# DIMNode012014.net
KiCad netlist of a schematic drawn in Altium Designer
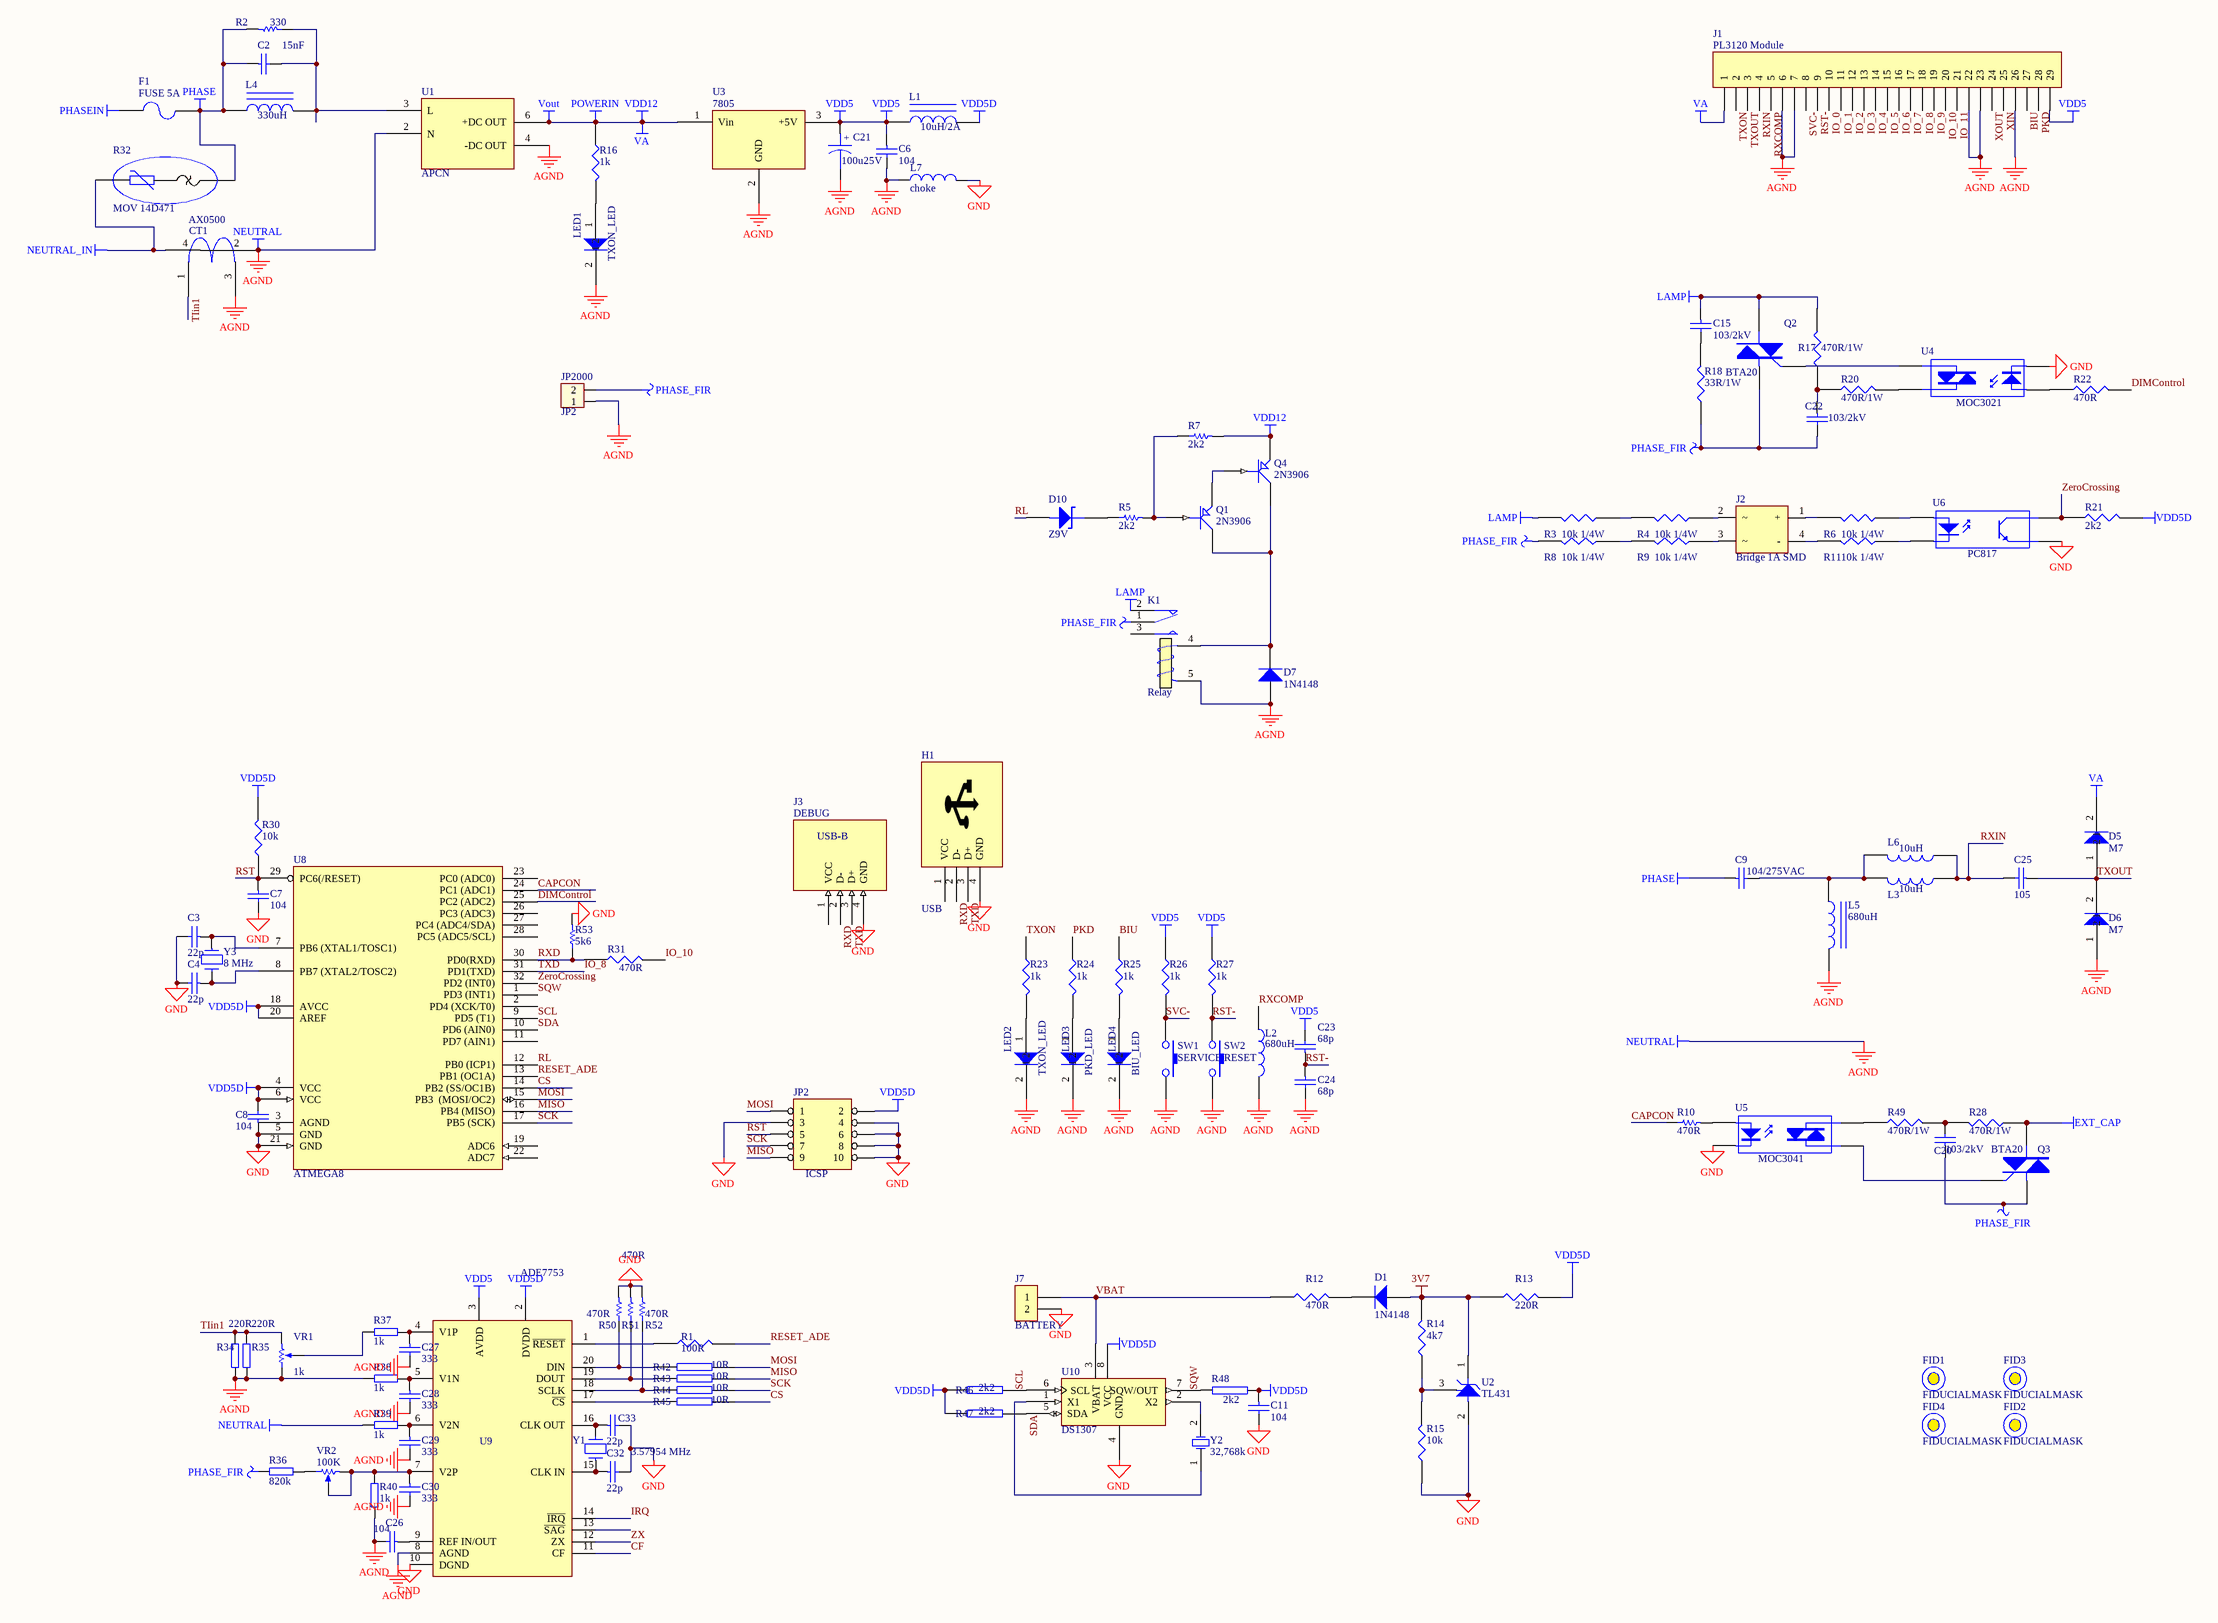
[diagram p0: DIMNode012014.SchDoc]

(export (version "E")
  (design (tool "Eeschema 10.0.6"))
  (components
    (comp (ref "C2")
      (value "15nF")
      (footprint "CAPNTO5.08-7.37x3.94")
      (description "Capacitor")
      (libsource (lib "") (part "CAP_1"))
    )
    (comp (ref "C3") (value "22p") (footprint "2012[0805]") (libsource (lib "*") (part "CAP")))
    (comp (ref "C4") (value "22p") (footprint "2012[0805]") (libsource (lib "*") (part "CAP")))
    (comp (ref "C6")
      (value "104")
      (footprint "2012[0805]")
      (description "Capacitor")
      (libsource (lib "") (part "CAP_1"))
    )
    (comp (ref "C7")
      (value "104")
      (footprint "2012[0805]")
      (description "Capacitor")
      (libsource (lib "") (part "CAP_1"))
    )
    (comp (ref "C8")
      (value "104")
      (footprint "2012[0805]")
      (description "Capacitor")
      (libsource (lib "") (part "CAP_1"))
    )
    (comp (ref "C9")
      (value "104/275VAC")
      (footprint "100n400v")
      (description "Capacitor")
      (libsource (lib "") (part "CAP_1"))
    )
    (comp (ref "C11")
      (value "104")
      (footprint "2012[0805]")
      (description "Capacitor")
      (libsource (lib "") (part "CAP_1"))
    )
    (comp (ref "C15")
      (value "103/2kV")
      (footprint "104TO")
      (description "Capacitor")
      (libsource (lib "") (part "CAP_1"))
    )
    (comp (ref "C20")
      (value "103/2kV")
      (footprint "104TO")
      (description "Capacitor")
      (libsource (lib "") (part "CAP_1"))
    )
    (comp (ref "C21")
      (value "100u25V")
      (footprint "TC7360-2924")
      (description "Capacitor")
      (libsource (lib "*") (part "CAPACITOR POL"))
    )
    (comp (ref "C22")
      (value "103/2kV")
      (footprint "104TO")
      (description "Capacitor")
      (libsource (lib "") (part "CAP_1"))
    )
    (comp (ref "C23")
      (value "68p")
      (footprint "2012[0805]")
      (description "Capacitor")
      (libsource (lib "") (part "CAP_1"))
    )
    (comp (ref "C24")
      (value "68p")
      (footprint "2012[0805]")
      (description "Capacitor")
      (libsource (lib "") (part "CAP_1"))
    )
    (comp (ref "C25")
      (value "105")
      (footprint "CSIP3")
      (description "Capacitor")
      (libsource (lib "") (part "CAP_1"))
    )
    (comp (ref "C26") (value "104") (footprint "2012[0805]") (libsource (lib "*") (part "CAP")))
    (comp (ref "C27") (value "333") (footprint "2012[0805]") (libsource (lib "*") (part "CAP")))
    (comp (ref "C28") (value "333") (footprint "2012[0805]") (libsource (lib "*") (part "CAP")))
    (comp (ref "C29") (value "333") (footprint "2012[0805]") (libsource (lib "*") (part "CAP")))
    (comp (ref "C30") (value "333") (footprint "2012[0805]") (libsource (lib "*") (part "CAP")))
    (comp (ref "C32") (value "22p") (footprint "2012[0805]") (libsource (lib "*") (part "CAP")))
    (comp (ref "C33") (value "22p") (footprint "2012[0805]") (libsource (lib "*") (part "CAP")))
    (comp (ref "CT1") (value "AX0500") (footprint "CT-NHO") (libsource (lib "Schlib1") (part "AX-0500")))
    (comp (ref "D1")
      (value "1N4148")
      (footprint "SOD-80/MLL34")
      (description "1 Amp General Purpose Rectifier")
      (fields (field (name "PUBLISHER") "Altium Limited"))
      (libsource (lib "*") (part "Diode 1N4007"))
    )
    (comp (ref "D5") (value "M7") (footprint "MELF-D5022-2009") (libsource (lib "*") (part "DIODE")))
    (comp (ref "D6") (value "M7") (footprint "MELF-D5022-2009") (libsource (lib "*") (part "DIODE")))
    (comp (ref "D7")
      (value "1N4148")
      (footprint "SOD-80/MLL34")
      (description "1 Amp General Purpose Rectifier")
      (fields (field (name "PUBLISHER") "Altium Limited"))
      (libsource (lib "*") (part "Diode 1N4007"))
    )
    (comp (ref "D10")
      (value "Z9V")
      (footprint "SOD-80/MLL34")
      (description "Zener Diode")
      (libsource (lib "*") (part "ZENER2"))
    )
    (comp (ref "F1")
      (value "FUSE 5A")
      (footprint "FUSE2")
      (description "Fuse")
      (libsource (lib "*") (part "FUSE2"))
    )
    (comp (ref "FID1")
      (value "FIDUCIALMASK")
      (footprint "FIDUCIALMASK")
      (libsource (lib "*") (part "FIDUCIALMASK"))
    )
    (comp (ref "FID2")
      (value "FIDUCIALMASK")
      (footprint "FIDUCIALMASK")
      (libsource (lib "*") (part "FIDUCIALMASK"))
    )
    (comp (ref "FID3")
      (value "FIDUCIALMASK")
      (footprint "FIDUCIALMASK")
      (libsource (lib "*") (part "FIDUCIALMASK"))
    )
    (comp (ref "FID4")
      (value "FIDUCIALMASK")
      (footprint "FIDUCIALMASK")
      (libsource (lib "*") (part "FIDUCIALMASK"))
    )
    (comp (ref "H1") (value "USB") (footprint "USB-B-STRANGE") (libsource (lib "Schematic") (part "USB")))
    (comp (ref "J1")
      (value "PL3120 Module")
      (footprint "ECHELONMODULE")
      (description "Connector")
      (libsource (lib "*") (part "CON29"))
    )
    (comp (ref "J2")
      (value "Bridge 1A SMD")
      (footprint "CAUSMD")
      (description "Diode Bridge")
      (libsource (lib "Schematic") (part "Diode Bridge Flate"))
    )
    (comp (ref "J3") (value "DEBUG") (footprint "SJ-3515") (libsource (lib "*") (part "USB_B")))
    (comp (ref "J7")
      (value "BATTERY")
      (footprint "pincucao")
      (description "Connector")
      (libsource (lib "*") (part "CON2"))
    )
    (comp (ref "JP2") (value "ICSP") (footprint "IDC10") (libsource (lib "*") (part "HEADER 5X2")))
    (comp (ref "JP2000")
      (value "JP2")
      (footprint "HED2")
      (description "Connector 2")
      (libsource (lib "syhaunguyen") (part "Con2"))
    )
    (comp (ref "K1")
      (value "Relay")
      (footprint "Relayvuong")
      (description "SPDT Relay")
      (fields (field (name "PUBLISHER") "Altium Limited"))
      (libsource (lib "*") (part "Relay"))
    )
    (comp (ref "L1") (value "10uH/2A") (libsource (lib "*") (part "INDUCTOR IRON")))
    (comp (ref "L2") (value "680uH") (footprint "AXIAL0.4") (libsource (lib "*") (part "INDUCTOR")))
    (comp (ref "L3") (value "10uH") (footprint "AXIAL0.4") (libsource (lib "*") (part "INDUCTOR")))
    (comp (ref "L4") (value "330uH") (footprint "CAMTRONDUNG") (libsource (lib "*") (part "INDUCTOR IRON")))
    (comp (ref "L5") (value "680uH") (footprint "axial0.4") (libsource (lib "*") (part "INDUCTOR IRON")))
    (comp (ref "L6") (value "10uH") (footprint "AXIAL0.4") (libsource (lib "*") (part "INDUCTOR")))
    (comp (ref "L7")
      (value "choke")
      (footprint "axial0.3")
      (fields (field (name "PUBLISHER") "Altium Limited"))
      (libsource (lib "Miscellaneous Devices") (part "Inductor"))
    )
    (comp (ref "LED1") (value "TXON_LED") (footprint "LED0805") (libsource (lib "*") (part "DIODE")))
    (comp (ref "LED2") (value "TXON_LED") (footprint "LED0805") (libsource (lib "*") (part "DIODE")))
    (comp (ref "LED3") (value "PKD_LED") (footprint "LED0805") (libsource (lib "*") (part "DIODE")))
    (comp (ref "LED4") (value "BIU_LED") (footprint "LED0805") (libsource (lib "*") (part "DIODE")))
    (comp (ref "Q1")
      (value "2N3906")
      (footprint "SOT-23")
      (description "PNP Transistor")
      (libsource (lib "*") (part "PNP1"))
    )
    (comp (ref "Q2") (value "BTA20") (footprint "TO254") (libsource (lib "*") (part "TRIAC")))
    (comp (ref "Q3") (value "BTA20") (footprint "TO254") (libsource (lib "*") (part "TRIAC")))
    (comp (ref "Q4")
      (value "2N3906")
      (footprint "SOT-23")
      (description "PNP Transistor")
      (libsource (lib "*") (part "PNP1"))
    )
    (comp (ref "R1") (value "100R") (footprint "2012[0805]") (libsource (lib "*") (part "RES1")))
    (comp (ref "R2")
      (value "330")
      (footprint "3216[1206]")
      (description "Semiconductor Resistor")
      (fields (field (name "PUBLISHER") "Altium Limited"))
      (libsource (lib "*") (part "Res Semi"))
    )
    (comp (ref "R3") (value "10k 1/4W") (footprint "3216[1206]") (libsource (lib "*") (part "RES1")))
    (comp (ref "R4") (value "10k 1/4W") (footprint "3216[1206]") (libsource (lib "*") (part "RES1")))
    (comp (ref "R5")
      (value "2k2")
      (footprint "2012[0805]")
      (description "Semiconductor Resistor")
      (fields (field (name "PUBLISHER") "Altium Limited"))
      (libsource (lib "*") (part "Res Semi"))
    )
    (comp (ref "R6") (value "10k 1/4W") (footprint "3216[1206]") (libsource (lib "*") (part "RES1")))
    (comp (ref "R7")
      (value "2k2")
      (footprint "2012[0805]")
      (description "Semiconductor Resistor")
      (fields (field (name "PUBLISHER") "Altium Limited"))
      (libsource (lib "*") (part "Res Semi"))
    )
    (comp (ref "R8") (value "10k 1/4W") (footprint "3216[1206]") (libsource (lib "*") (part "RES1")))
    (comp (ref "R9") (value "10k 1/4W") (footprint "3216[1206]") (libsource (lib "*") (part "RES1")))
    (comp (ref "R10")
      (value "470R")
      (footprint "2012[0805]")
      (description "Semiconductor Resistor")
      (fields (field (name "PUBLISHER") "Altium Limited"))
      (libsource (lib "*") (part "Res Semi"))
    )
    (comp (ref "R11") (value "10k 1/4W") (footprint "3216[1206]") (libsource (lib "*") (part "RES1")))
    (comp (ref "R12") (value "470R") (footprint "2012[0805]") (libsource (lib "*") (part "RES1")))
    (comp (ref "R13") (value "220R") (footprint "2012[0805]") (libsource (lib "*") (part "RES1")))
    (comp (ref "R14") (value "4k7") (footprint "2012[0805]") (libsource (lib "*") (part "RES1")))
    (comp (ref "R15") (value "10k") (footprint "2012[0805]") (libsource (lib "*") (part "RES1")))
    (comp (ref "R16") (value "1k") (footprint "2012[0805]") (libsource (lib "*") (part "RES1")))
    (comp (ref "R17") (value "470R/1W") (footprint "AXIAL0.5") (libsource (lib "*") (part "RES1")))
    (comp (ref "R18") (value "33R/1W") (footprint "R1W_dung") (libsource (lib "*") (part "RES1")))
    (comp (ref "R20") (value "470R/1W") (footprint "R1W_DUNG") (libsource (lib "*") (part "RES1")))
    (comp (ref "R21") (value "2k2") (footprint "2012[0805]") (libsource (lib "*") (part "RES1")))
    (comp (ref "R22") (value "470R") (footprint "2012[0805]") (libsource (lib "*") (part "RES1")))
    (comp (ref "R23") (value "1k") (footprint "2012[0805]") (libsource (lib "*") (part "RES1")))
    (comp (ref "R24") (value "1k") (footprint "2012[0805]") (libsource (lib "*") (part "RES1")))
    (comp (ref "R25") (value "1k") (footprint "2012[0805]") (libsource (lib "*") (part "RES1")))
    (comp (ref "R26") (value "1k") (footprint "2012[0805]") (libsource (lib "*") (part "RES1")))
    (comp (ref "R27") (value "1k") (footprint "2012[0805]") (libsource (lib "*") (part "RES1")))
    (comp (ref "R28") (value "470R/1W") (footprint "R1W_dung") (libsource (lib "*") (part "RES1")))
    (comp (ref "R30") (value "10k") (footprint "2012[0805]") (libsource (lib "*") (part "RES1")))
    (comp (ref "R31") (value "470R") (footprint "2012[0805]") (libsource (lib "*") (part "RES1")))
    (comp (ref "R32") (value "MOV 14D471") (footprint "MOV471") (libsource (lib "*") (part "MOV")))
    (comp (ref "R34") (value "220R") (footprint "2012[0805]") (libsource (lib "") (part "RES2_1")))
    (comp (ref "R35") (value "220R") (footprint "2012[0805]") (libsource (lib "") (part "RES2_1")))
    (comp (ref "R36") (value "820k") (footprint "1206") (libsource (lib "") (part "RES2_1")))
    (comp (ref "R37") (value "1k") (footprint "2012[0805]") (libsource (lib "") (part "RES2_1")))
    (comp (ref "R38") (value "1k") (footprint "2012[0805]") (libsource (lib "") (part "RES2_1")))
    (comp (ref "R39") (value "1k") (footprint "2012[0805]") (libsource (lib "") (part "RES2_1")))
    (comp (ref "R40") (value "1k") (footprint "2012[0805]") (libsource (lib "") (part "RES2_1")))
    (comp (ref "R42") (value "10R") (footprint "2012[0805]") (libsource (lib "*") (part "RES2")))
    (comp (ref "R43") (value "10R") (footprint "2012[0805]") (libsource (lib "*") (part "RES2")))
    (comp (ref "R44") (value "10R") (footprint "2012[0805]") (libsource (lib "*") (part "RES2")))
    (comp (ref "R45") (value "10R") (footprint "2012[0805]") (libsource (lib "*") (part "RES2")))
    (comp (ref "R46") (value "2k2") (footprint "2012[0805]") (libsource (lib "*") (part "RES2")))
    (comp (ref "R47") (value "2k2") (footprint "2012[0805]") (libsource (lib "*") (part "RES2")))
    (comp (ref "R48") (value "2k2") (footprint "2012[0805]") (libsource (lib "") (part "RES2_2")))
    (comp (ref "R49") (value "470R/1W") (footprint "R1W_DUNG") (libsource (lib "*") (part "RES1")))
    (comp (ref "R50")
      (value "470R")
      (footprint "2012[0805]")
      (description "Semiconductor Resistor")
      (fields (field (name "PUBLISHER") "*"))
      (libsource (lib "*") (part "Res Semi"))
    )
    (comp (ref "R51")
      (value "470R")
      (footprint "2012[0805]")
      (description "Semiconductor Resistor")
      (fields (field (name "PUBLISHER") "*"))
      (libsource (lib "*") (part "Res Semi"))
    )
    (comp (ref "R52")
      (value "470R")
      (footprint "2012[0805]")
      (description "Semiconductor Resistor")
      (fields (field (name "PUBLISHER") "*"))
      (libsource (lib "*") (part "Res Semi"))
    )
    (comp (ref "R53")
      (value "5k6")
      (footprint "2012[0805]")
      (description "Semiconductor Resistor")
      (fields (field (name "PUBLISHER") "*"))
      (libsource (lib "*") (part "Res Semi"))
    )
    (comp (ref "SW1") (value "SERVICE") (footprint "CTCHIPNGANG") (libsource (lib "*") (part "SW-PB")))
    (comp (ref "SW2") (value "RESET") (footprint "CTCHIPNGANG") (libsource (lib "*") (part "SW-PB")))
    (comp (ref "U1") (value "APCN") (footprint "APCN") (libsource (lib "Node v2013") (part "Component_1")))
    (comp (ref "U2")
      (value "TL431")
      (footprint "TL431")
      (description "Adjustable Precision Shunt Regulator")
      (libsource (lib "*") (part "TL431"))
    )
    (comp (ref "U3") (value "7805") (footprint "J7805") (libsource (lib "*") (part "MC7805T")))
    (comp (ref "U4") (value "MOC3021") (footprint "DIP6") (libsource (lib "*") (part "OPTOTRIAC")))
    (comp (ref "U5") (value "MOC3041") (footprint "DIP6") (libsource (lib "*") (part "OPTOTRIAC")))
    (comp (ref "U6")
      (value "PC817")
      (footprint "TLP521")
      (description "Optoisolator")
      (libsource (lib "*") (part "OPTOISO1"))
    )
    (comp (ref "U8")
      (value "ATMEGA8")
      (footprint "ATMEGA8")
      (description "TQFP package")
      (libsource (lib "*") (part "ATMEGA8-A"))
    )
    (comp (ref "U9") (value "ADE7753") (footprint "ADE775X") (libsource (lib "*") (part "ADE775X")))
    (comp (ref "U10")
      (value "DS1307")
      (footprint "SO-8")
      (description "64x8 SERIAL REAL TIME CLOCK")
      (libsource (lib "*") (part "DS1307(8)"))
    )
    (comp (ref "VR1")
      (value "1k")
      (footprint "BTXANH")
      (description "Potentiometer")
      (fields (field (name "PUBLISHER") "*"))
      (libsource (lib "*") (part "RPot"))
    )
    (comp (ref "VR2")
      (value "100K")
      (footprint "BTXANH")
      (description "Potentiometer")
      (fields (field (name "PUBLISHER") "*"))
      (libsource (lib "*") (part "RPot"))
    )
    (comp (ref "Y1")
      (value "3.57954 MHz")
      (footprint "XTAL")
      (description "Crystal")
      (libsource (lib "*") (part "CRYSTAL"))
    )
    (comp (ref "Y2")
      (value "32,768k")
      (footprint "R38")
      (description "Crystal Oscillator")
      (fields (field (name "PUBLISHER") "Altium Limited"))
      (libsource (lib "Miscellaneous Devices") (part "XTAL"))
    )
    (comp (ref "Y3")
      (value "8 MHz")
      (footprint "XTAL")
      (description "Crystal")
      (libsource (lib "*") (part "CRYSTAL"))
    )
  )
  (nets
    (net (code "1") (name "/BIU") (class "Default")
      (node (ref "J1") (pin "27") (pinfunction "27_27") (pintype "passive"))
      (node (ref "R25") (pin "1") (pinfunction "1_1") (pintype "passive"))
    )
    (net (code "2") (name "/CAPCON") (class "Default")
      (node (ref "R10") (pin "1") (pinfunction "1_1") (pintype "passive"))
      (node (ref "U8") (pin "24") (pinfunction "PC1_(ADC1)_24") (pintype "passive"))
    )
    (net (code "3") (name "/CF") (class "Default")
      (node (ref "U9") (pin "11") (pinfunction "CF_11") (pintype "passive"))
    )
    (net (code "4") (name "/CS") (class "Default")
      (node (ref "R45") (pin "1") (pinfunction "1_1") (pintype "passive"))
      (node (ref "U8") (pin "14") (pinfunction "PB2_(SS/OC1B)_14") (pintype "passive"))
    )
    (net (code "5") (name "/DIMControl") (class "Default")
      (node (ref "R22") (pin "2") (pinfunction "2_2") (pintype "passive"))
      (node (ref "U8") (pin "25") (pinfunction "PC2_(ADC2)_25") (pintype "passive"))
    )
    (net (code "6") (name "/IO_0") (class "Default")
      (node (ref "J1") (pin "10") (pinfunction "10_10") (pintype "passive"))
    )
    (net (code "7") (name "/IO_1") (class "Default")
      (node (ref "J1") (pin "11") (pinfunction "11_11") (pintype "passive"))
    )
    (net (code "8") (name "/IO_2") (class "Default")
      (node (ref "J1") (pin "12") (pinfunction "12_12") (pintype "passive"))
    )
    (net (code "9") (name "/IO_3") (class "Default")
      (node (ref "J1") (pin "13") (pinfunction "13_13") (pintype "passive"))
    )
    (net (code "10") (name "/IO_4") (class "Default")
      (node (ref "J1") (pin "14") (pinfunction "14_14") (pintype "passive"))
    )
    (net (code "11") (name "/IO_5") (class "Default")
      (node (ref "J1") (pin "15") (pinfunction "15_15") (pintype "passive"))
    )
    (net (code "12") (name "/IO_6") (class "Default")
      (node (ref "J1") (pin "16") (pinfunction "16_16") (pintype "passive"))
    )
    (net (code "13") (name "/IO_7") (class "Default")
      (node (ref "J1") (pin "17") (pinfunction "17_17") (pintype "passive"))
    )
    (net (code "14") (name "/IO_8") (class "Default")
      (node (ref "H1") (pin "3") (pinfunction "D+_3") (pintype "passive"))
      (node (ref "J1") (pin "18") (pinfunction "18_18") (pintype "passive"))
      (node (ref "J3") (pin "3") (pinfunction "D+_3") (pintype "input"))
      (node (ref "U8") (pin "31") (pinfunction "PD1(TXD)_31") (pintype "passive"))
    )
    (net (code "15") (name "/IO_9") (class "Default")
      (node (ref "J1") (pin "19") (pinfunction "19_19") (pintype "passive"))
    )
    (net (code "16") (name "/IO_10") (class "Default")
      (node (ref "J1") (pin "20") (pinfunction "20_20") (pintype "passive"))
      (node (ref "R31") (pin "2") (pinfunction "2_2") (pintype "passive"))
    )
    (net (code "17") (name "/IO_11") (class "Default")
      (node (ref "J1") (pin "21") (pinfunction "21_21") (pintype "passive"))
    )
    (net (code "18") (name "/IRQ") (class "Default")
      (node (ref "U9") (pin "14") (pinfunction "~{IRQ}_14") (pintype "passive"))
    )
    (net (code "19") (name "/MISO") (class "Default")
      (node (ref "JP2") (pin "9") (pinfunction "9_9") (pintype "passive"))
      (node (ref "R43") (pin "1") (pinfunction "1_1") (pintype "passive"))
      (node (ref "U8") (pin "16") (pinfunction "PB4_(MISO)_16") (pintype "passive"))
    )
    (net (code "20") (name "/MOSI") (class "Default")
      (node (ref "JP2") (pin "1") (pinfunction "1_1") (pintype "passive"))
      (node (ref "R42") (pin "1") (pinfunction "1_1") (pintype "passive"))
      (node (ref "U8") (pin "15") (pinfunction "PB3__(MOSI/OC2)_15") (pintype "bidirectional"))
    )
    (net (code "21") (name "/PKD") (class "Default")
      (node (ref "J1") (pin "28") (pinfunction "28_28") (pintype "passive"))
      (node (ref "R24") (pin "1") (pinfunction "1_1") (pintype "passive"))
    )
    (net (code "22") (name "/RESET_ADE") (class "Default")
      (node (ref "R1") (pin "2") (pinfunction "2_2") (pintype "passive"))
      (node (ref "U8") (pin "13") (pinfunction "PB1_(OC1A)_13") (pintype "passive"))
    )
    (net (code "23") (name "/RL") (class "Default")
      (node (ref "D10") (pin "1") (pinfunction "A_1") (pintype "passive"))
      (node (ref "U8") (pin "12") (pinfunction "PB0_(ICP1)_12") (pintype "passive"))
    )
    (net (code "24") (name "/RST") (class "Default")
      (node (ref "C7") (pin "1") (pinfunction "1_1") (pintype "passive"))
      (node (ref "JP2") (pin "5") (pinfunction "5_5") (pintype "passive"))
      (node (ref "R30") (pin "1") (pinfunction "1_1") (pintype "passive"))
      (node (ref "U8") (pin "29") (pinfunction "PC6(/RESET)_29") (pintype "passive"))
    )
    (net (code "25") (name "/RST-") (class "Default")
      (node (ref "C23") (pin "1") (pinfunction "1_1") (pintype "passive"))
      (node (ref "C24") (pin "1") (pinfunction "1_1") (pintype "passive"))
      (node (ref "J1") (pin "9") (pinfunction "9_9") (pintype "passive"))
      (node (ref "R27") (pin "2") (pinfunction "2_2") (pintype "passive"))
      (node (ref "SW2") (pin "1") (pinfunction "1_1") (pintype "passive"))
    )
    (net (code "26") (name "/RXCOMP") (class "Default")
      (node (ref "J1") (pin "5") (pinfunction "5_5") (pintype "passive"))
      (node (ref "L2") (pin "1") (pinfunction "1_1") (pintype "passive"))
    )
    (net (code "27") (name "/RXD") (class "Default")
      (node (ref "H1") (pin "2") (pinfunction "D-_2") (pintype "passive"))
      (node (ref "J3") (pin "2") (pinfunction "D-_2") (pintype "input"))
      (node (ref "R31") (pin "1") (pinfunction "1_1") (pintype "passive"))
      (node (ref "R53") (pin "1") (pinfunction "1_1") (pintype "passive"))
      (node (ref "U8") (pin "30") (pinfunction "PD0(RXD)_30") (pintype "passive"))
    )
    (net (code "28") (name "/RXIN") (class "Default")
      (node (ref "C25") (pin "2") (pinfunction "2_2") (pintype "passive"))
      (node (ref "J1") (pin "4") (pinfunction "4_4") (pintype "passive"))
      (node (ref "L3") (pin "1") (pinfunction "1_1") (pintype "passive"))
      (node (ref "L6") (pin "1") (pinfunction "1_1") (pintype "passive"))
    )
    (net (code "29") (name "/SCK") (class "Default")
      (node (ref "JP2") (pin "7") (pinfunction "7_7") (pintype "passive"))
      (node (ref "R44") (pin "1") (pinfunction "1_1") (pintype "passive"))
      (node (ref "U8") (pin "17") (pinfunction "PB5_(SCK)_17") (pintype "passive"))
    )
    (net (code "30") (name "/SCL") (class "Default")
      (node (ref "R46") (pin "1") (pinfunction "1_1") (pintype "passive"))
      (node (ref "U10") (pin "6") (pinfunction "SCL_6") (pintype "input"))
      (node (ref "U8") (pin "9") (pinfunction "PD5_(T1)_9") (pintype "passive"))
    )
    (net (code "31") (name "/SDA") (class "Default")
      (node (ref "R47") (pin "1") (pinfunction "1_1") (pintype "passive"))
      (node (ref "U10") (pin "5") (pinfunction "SDA_5") (pintype "bidirectional"))
      (node (ref "U8") (pin "10") (pinfunction "PD6_(AIN0)_10") (pintype "passive"))
    )
    (net (code "32") (name "/SQW") (class "Default")
      (node (ref "R48") (pin "1") (pinfunction "1_1") (pintype "passive"))
      (node (ref "U10") (pin "7") (pinfunction "SQW/OUT_7") (pintype "output"))
      (node (ref "U8") (pin "1") (pinfunction "PD3_(INT1)_1") (pintype "passive"))
    )
    (net (code "33") (name "/SVC-") (class "Default")
      (node (ref "J1") (pin "8") (pinfunction "8_8") (pintype "passive"))
      (node (ref "R26") (pin "2") (pinfunction "2_2") (pintype "passive"))
      (node (ref "SW1") (pin "1") (pinfunction "1_1") (pintype "passive"))
    )
    (net (code "34") (name "/TIin1") (class "Default")
      (node (ref "CT1") (pin "1") (pinfunction "OUT1_1") (pintype "passive"))
      (node (ref "R34") (pin "2") (pinfunction "2_2") (pintype "passive"))
      (node (ref "R35") (pin "2") (pinfunction "2_2") (pintype "passive"))
      (node (ref "VR1") (pin "3") (pinfunction "BOT_3") (pintype "passive"))
    )
    (net (code "35") (name "/TXON") (class "Default")
      (node (ref "J1") (pin "2") (pinfunction "2_2") (pintype "passive"))
      (node (ref "R23") (pin "1") (pinfunction "1_1") (pintype "passive"))
    )
    (net (code "36") (name "/TXOUT") (class "Default")
      (node (ref "C25") (pin "1") (pinfunction "1_1") (pintype "passive"))
      (node (ref "D5") (pin "1") (pinfunction "1_1") (pintype "passive"))
      (node (ref "D6") (pin "2") (pinfunction "2_2") (pintype "passive"))
      (node (ref "J1") (pin "3") (pinfunction "3_3") (pintype "passive"))
    )
    (net (code "37") (name "/VBAT") (class "Default")
      (node (ref "J7") (pin "1") (pinfunction "1_1") (pintype "passive"))
      (node (ref "R12") (pin "1") (pinfunction "1_1") (pintype "passive"))
      (node (ref "U10") (pin "3") (pinfunction "VBAT_3") (pintype "power_in"))
    )
    (net (code "38") (name "/XIN") (class "Default")
      (node (ref "J1") (pin "25") (pinfunction "25_25") (pintype "passive"))
    )
    (net (code "39") (name "/XOUT") (class "Default")
      (node (ref "J1") (pin "24") (pinfunction "24_24") (pintype "passive"))
    )
    (net (code "40") (name "/ZX") (class "Default")
      (node (ref "U9") (pin "12") (pinfunction "ZX_12") (pintype "passive"))
    )
    (net (code "41") (name "/ZeroCrossing") (class "Default")
      (node (ref "R21") (pin "1") (pinfunction "1_1") (pintype "passive"))
      (node (ref "U6") (pin "3") (pinfunction "C_3") (pintype "passive"))
      (node (ref "U8") (pin "32") (pinfunction "PD2_(INT0)_32") (pintype "passive"))
    )
    (net (code "42") (name "3V7") (class "Default")
      (node (ref "D1") (pin "1") (pinfunction "A_1") (pintype "passive"))
      (node (ref "R13") (pin "1") (pinfunction "1_1") (pintype "passive"))
      (node (ref "R14") (pin "2") (pinfunction "2_2") (pintype "passive"))
      (node (ref "U2") (pin "1") (pinfunction "K_1") (pintype "passive"))
    )
    (net (code "43") (name "AGND") (class "Default")
      (node (ref "C21") (pin "2") (pinfunction "2_2") (pintype "passive"))
      (node (ref "C24") (pin "2") (pinfunction "2_2") (pintype "passive"))
      (node (ref "C26") (pin "2") (pinfunction "2_2") (pintype "passive"))
      (node (ref "C27") (pin "2") (pinfunction "2_2") (pintype "passive"))
      (node (ref "C28") (pin "2") (pinfunction "2_2") (pintype "passive"))
      (node (ref "C29") (pin "2") (pinfunction "2_2") (pintype "passive"))
      (node (ref "C30") (pin "2") (pinfunction "2_2") (pintype "passive"))
      (node (ref "C6") (pin "2") (pinfunction "2_2") (pintype "passive"))
      (node (ref "CT1") (pin "2") (pinfunction "ACin_2") (pintype "passive"))
      (node (ref "CT1") (pin "3") (pinfunction "OUT2_3") (pintype "passive"))
      (node (ref "D6") (pin "1") (pinfunction "1_1") (pintype "passive"))
      (node (ref "D7") (pin "1") (pinfunction "A_1") (pintype "passive"))
      (node (ref "J1") (pin "22") (pinfunction "22_22") (pintype "passive"))
      (node (ref "J1") (pin "23") (pinfunction "23_23") (pintype "passive"))
      (node (ref "J1") (pin "26") (pinfunction "26_26") (pintype "passive"))
      (node (ref "J1") (pin "6") (pinfunction "6_6") (pintype "passive"))
      (node (ref "J1") (pin "7") (pinfunction "7_7") (pintype "passive"))
      (node (ref "JP2000") (pin "1") (pinfunction "1_1") (pintype "passive"))
      (node (ref "K1") (pin "5") (pinfunction "T2_5") (pintype "passive"))
      (node (ref "L2") (pin "2") (pinfunction "2_2") (pintype "passive"))
      (node (ref "L5") (pin "2") (pinfunction "2_2") (pintype "passive"))
      (node (ref "L7") (pin "1") (pinfunction "1_1") (pintype "passive"))
      (node (ref "LED1") (pin "2") (pinfunction "2_2") (pintype "passive"))
      (node (ref "LED2") (pin "2") (pinfunction "2_2") (pintype "passive"))
      (node (ref "LED3") (pin "2") (pinfunction "2_2") (pintype "passive"))
      (node (ref "LED4") (pin "2") (pinfunction "2_2") (pintype "passive"))
      (node (ref "R34") (pin "1") (pinfunction "1_1") (pintype "passive"))
      (node (ref "R35") (pin "1") (pinfunction "1_1") (pintype "passive"))
      (node (ref "R38") (pin "2") (pinfunction "2_2") (pintype "passive"))
      (node (ref "R39") (pin "2") (pinfunction "2_2") (pintype "passive"))
      (node (ref "R40") (pin "1") (pinfunction "1_1") (pintype "passive"))
      (node (ref "SW1") (pin "2") (pinfunction "2_2") (pintype "passive"))
      (node (ref "SW2") (pin "2") (pinfunction "2_2") (pintype "passive"))
      (node (ref "U1") (pin "2") (pinfunction "N_2") (pintype "passive"))
      (node (ref "U1") (pin "4") (pinfunction "-DC_OUT_4") (pintype "passive"))
      (node (ref "U3") (pin "2") (pinfunction "GND_2") (pintype "passive"))
      (node (ref "U9") (pin "8") (pinfunction "AGND_8") (pintype "passive"))
      (node (ref "VR1") (pin "1") (pinfunction "TOP_1") (pintype "passive"))
    )
    (net (code "44") (name "EXT_CAP") (class "Default")
      (node (ref "Q3") (pin "2") (pinfunction "T_2") (pintype "passive"))
      (node (ref "R28") (pin "1") (pinfunction "1_1") (pintype "passive"))
    )
    (net (code "45") (name "GND") (class "Default")
      (node (ref "C11") (pin "2") (pinfunction "2_2") (pintype "passive"))
      (node (ref "C3") (pin "2") (pinfunction "2_2") (pintype "passive"))
      (node (ref "C32") (pin "2") (pinfunction "2_2") (pintype "passive"))
      (node (ref "C33") (pin "2") (pinfunction "2_2") (pintype "passive"))
      (node (ref "C4") (pin "2") (pinfunction "2_2") (pintype "passive"))
      (node (ref "C7") (pin "2") (pinfunction "2_2") (pintype "passive"))
      (node (ref "C8") (pin "1") (pinfunction "1_1") (pintype "passive"))
      (node (ref "H1") (pin "4") (pinfunction "GND_4") (pintype "passive"))
      (node (ref "J3") (pin "4") (pinfunction "GND_4") (pintype "input"))
      (node (ref "J7") (pin "2") (pinfunction "2_2") (pintype "passive"))
      (node (ref "JP2") (pin "10") (pinfunction "10_10") (pintype "passive"))
      (node (ref "JP2") (pin "3") (pinfunction "3_3") (pintype "passive"))
      (node (ref "JP2") (pin "4") (pinfunction "4_4") (pintype "passive"))
      (node (ref "JP2") (pin "6") (pinfunction "6_6") (pintype "passive"))
      (node (ref "JP2") (pin "8") (pinfunction "8_8") (pintype "passive"))
      (node (ref "L7") (pin "2") (pinfunction "2_2") (pintype "passive"))
      (node (ref "R15") (pin "1") (pinfunction "1_1") (pintype "passive"))
      (node (ref "R50") (pin "2") (pinfunction "2_2") (pintype "passive"))
      (node (ref "R51") (pin "2") (pinfunction "2_2") (pintype "passive"))
      (node (ref "R52") (pin "2") (pinfunction "2_2") (pintype "passive"))
      (node (ref "R53") (pin "2") (pinfunction "2_2") (pintype "passive"))
      (node (ref "U10") (pin "4") (pinfunction "GND_4") (pintype "power_in"))
      (node (ref "U2") (pin "2") (pinfunction "A_2") (pintype "passive"))
      (node (ref "U4") (pin "2") (pinfunction "K_2") (pintype "passive"))
      (node (ref "U5") (pin "2") (pinfunction "K_2") (pintype "passive"))
      (node (ref "U6") (pin "4") (pinfunction "E_4") (pintype "passive"))
      (node (ref "U8") (pin "21") (pinfunction "GND_21") (pintype "input"))
      (node (ref "U8") (pin "3") (pinfunction "AGND_3") (pintype "passive"))
      (node (ref "U8") (pin "5") (pinfunction "GND_5") (pintype "passive"))
      (node (ref "U9") (pin "10") (pinfunction "DGND_10") (pintype "passive"))
    )
    (net (code "46") (name "LAMP") (class "Default")
      (node (ref "C15") (pin "1") (pinfunction "1_1") (pintype "passive"))
      (node (ref "K1") (pin "2") (pinfunction "NC_2") (pintype "passive"))
      (node (ref "Q2") (pin "2") (pinfunction "T_2") (pintype "passive"))
      (node (ref "R17") (pin "2") (pinfunction "2_2") (pintype "passive"))
      (node (ref "R3") (pin "2") (pinfunction "2_2") (pintype "passive"))
    )
    (net (code "47") (name "NEUTRAL_IN") (class "Default")
      (node (ref "CT1") (pin "4") (pinfunction "ACout_4") (pintype "passive"))
      (node (ref "R32") (pin "2") (pinfunction "2_2") (pintype "passive"))
    )
    (net (code "48") (name "Net-(C9-Pad2)") (class "Default")
      (node (ref "C9") (pin "2") (pinfunction "2_2") (pintype "passive"))
      (node (ref "L3") (pin "2") (pinfunction "2_2") (pintype "passive"))
      (node (ref "L5") (pin "1") (pinfunction "1_1") (pintype "passive"))
      (node (ref "L6") (pin "2") (pinfunction "2_2") (pintype "passive"))
    )
    (net (code "49") (name "Net-(C15-Pad2)") (class "Default")
      (node (ref "C15") (pin "2") (pinfunction "2_2") (pintype "passive"))
      (node (ref "R18") (pin "2") (pinfunction "2_2") (pintype "passive"))
    )
    (net (code "50") (name "Net-(C20-Pad2)") (class "Default")
      (node (ref "C20") (pin "2") (pinfunction "2_2") (pintype "passive"))
      (node (ref "R28") (pin "2") (pinfunction "2_2") (pintype "passive"))
      (node (ref "R49") (pin "2") (pinfunction "2_2") (pintype "passive"))
    )
    (net (code "51") (name "Net-(C22-Pad1)") (class "Default")
      (node (ref "C22") (pin "1") (pinfunction "1_1") (pintype "passive"))
      (node (ref "R17") (pin "1") (pinfunction "1_1") (pintype "passive"))
      (node (ref "R20") (pin "1") (pinfunction "1_1") (pintype "passive"))
    )
    (net (code "52") (name "Net-(D1-K)") (class "Default")
      (node (ref "D1") (pin "2") (pinfunction "K_2") (pintype "passive"))
      (node (ref "R12") (pin "2") (pinfunction "2_2") (pintype "passive"))
    )
    (net (code "53") (name "Net-(D7-K)") (class "Default")
      (node (ref "D7") (pin "2") (pinfunction "K_2") (pintype "passive"))
      (node (ref "K1") (pin "4") (pinfunction "T1_4") (pintype "passive"))
      (node (ref "Q1") (pin "3") (pinfunction "C_3") (pintype "passive"))
      (node (ref "Q4") (pin "3") (pinfunction "C_3") (pintype "passive"))
    )
    (net (code "54") (name "Net-(D10-K)") (class "Default")
      (node (ref "D10") (pin "2") (pinfunction "K_2") (pintype "passive"))
      (node (ref "R5") (pin "1") (pinfunction "1_1") (pintype "passive"))
    )
    (net (code "55") (name "Net-(J2-+)") (class "Default")
      (node (ref "J2") (pin "1") (pinfunction "+_1") (pintype "passive"))
      (node (ref "R6") (pin "2") (pinfunction "2_2") (pintype "passive"))
    )
    (net (code "56") (name "Net-(J2--)") (class "Default")
      (node (ref "J2") (pin "4") (pinfunction "-_4") (pintype "passive"))
      (node (ref "R11") (pin "2") (pinfunction "2_2") (pintype "passive"))
    )
    (net (code "57") (name "Net-(J2-~-Pad2)") (class "Default")
      (node (ref "J2") (pin "2") (pinfunction "~_2") (pintype "passive"))
      (node (ref "R4") (pin "1") (pinfunction "1_1") (pintype "passive"))
    )
    (net (code "58") (name "Net-(J2-~-Pad3)") (class "Default")
      (node (ref "J2") (pin "3") (pinfunction "~_3") (pintype "passive"))
      (node (ref "R9") (pin "1") (pinfunction "1_1") (pintype "passive"))
    )
    (net (code "59") (name "Net-(LED1-Pad1)") (class "Default")
      (node (ref "LED1") (pin "1") (pinfunction "1_1") (pintype "passive"))
      (node (ref "R16") (pin "2") (pinfunction "2_2") (pintype "passive"))
    )
    (net (code "60") (name "Net-(LED2-Pad1)") (class "Default")
      (node (ref "LED2") (pin "1") (pinfunction "1_1") (pintype "passive"))
      (node (ref "R23") (pin "2") (pinfunction "2_2") (pintype "passive"))
    )
    (net (code "61") (name "Net-(LED3-Pad1)") (class "Default")
      (node (ref "LED3") (pin "1") (pinfunction "1_1") (pintype "passive"))
      (node (ref "R24") (pin "2") (pinfunction "2_2") (pintype "passive"))
    )
    (net (code "62") (name "Net-(LED4-Pad1)") (class "Default")
      (node (ref "LED4") (pin "1") (pinfunction "1_1") (pintype "passive"))
      (node (ref "R25") (pin "2") (pinfunction "2_2") (pintype "passive"))
    )
    (net (code "63") (name "Net-(Q1-B)") (class "Default")
      (node (ref "Q1") (pin "1") (pinfunction "B_1") (pintype "input"))
      (node (ref "R5") (pin "2") (pinfunction "2_2") (pintype "passive"))
      (node (ref "R7") (pin "1") (pinfunction "1_1") (pintype "passive"))
    )
    (net (code "64") (name "Net-(Q1-E)") (class "Default")
      (node (ref "Q1") (pin "2") (pinfunction "E_2") (pintype "passive"))
      (node (ref "Q4") (pin "1") (pinfunction "B_1") (pintype "input"))
    )
    (net (code "65") (name "Net-(Q2-G)") (class "Default")
      (node (ref "Q2") (pin "3") (pinfunction "G_3") (pintype "passive"))
      (node (ref "U4") (pin "4") (pinfunction "A/K_4") (pintype "passive"))
    )
    (net (code "66") (name "Net-(Q3-G)") (class "Default")
      (node (ref "Q3") (pin "3") (pinfunction "G_3") (pintype "passive"))
      (node (ref "U5") (pin "4") (pinfunction "A/K_4") (pintype "passive"))
    )
    (net (code "67") (name "Net-(R3-Pad1)") (class "Default")
      (node (ref "R3") (pin "1") (pinfunction "1_1") (pintype "passive"))
      (node (ref "R4") (pin "2") (pinfunction "2_2") (pintype "passive"))
    )
    (net (code "68") (name "Net-(R8-Pad1)") (class "Default")
      (node (ref "R8") (pin "1") (pinfunction "1_1") (pintype "passive"))
      (node (ref "R9") (pin "2") (pinfunction "2_2") (pintype "passive"))
    )
    (net (code "69") (name "Net-(R20-Pad2)") (class "Default")
      (node (ref "R20") (pin "2") (pinfunction "2_2") (pintype "passive"))
      (node (ref "U4") (pin "6") (pinfunction "A/K_6") (pintype "passive"))
    )
    (net (code "70") (name "Net-(R49-Pad1)") (class "Default")
      (node (ref "R49") (pin "1") (pinfunction "1_1") (pintype "passive"))
      (node (ref "U5") (pin "6") (pinfunction "A/K_6") (pintype "passive"))
    )
    (net (code "71") (name "Net-(U1-L)") (class "Default")
      (node (ref "C2") (pin "2") (pinfunction "2_2") (pintype "passive"))
      (node (ref "L4") (pin "2") (pinfunction "2_2") (pintype "passive"))
      (node (ref "R2") (pin "1") (pinfunction "1_1") (pintype "passive"))
      (node (ref "U1") (pin "3") (pinfunction "L_3") (pintype "passive"))
    )
    (net (code "72") (name "Net-(U2-R)") (class "Default")
      (node (ref "R14") (pin "1") (pinfunction "1_1") (pintype "passive"))
      (node (ref "R15") (pin "2") (pinfunction "2_2") (pintype "passive"))
      (node (ref "U2") (pin "3") (pinfunction "R_3") (pintype "passive"))
    )
    (net (code "73") (name "Net-(U4-A)") (class "Default")
      (node (ref "R22") (pin "1") (pinfunction "1_1") (pintype "passive"))
      (node (ref "U4") (pin "1") (pinfunction "A_1") (pintype "passive"))
    )
    (net (code "74") (name "Net-(U5-A)") (class "Default")
      (node (ref "R10") (pin "2") (pinfunction "2_2") (pintype "passive"))
      (node (ref "U5") (pin "1") (pinfunction "A_1") (pintype "passive"))
    )
    (net (code "75") (name "Net-(U6-A)") (class "Default")
      (node (ref "R6") (pin "1") (pinfunction "1_1") (pintype "passive"))
      (node (ref "U6") (pin "1") (pinfunction "A_1") (pintype "passive"))
    )
    (net (code "76") (name "Net-(U6-K)") (class "Default")
      (node (ref "R11") (pin "1") (pinfunction "1_1") (pintype "passive"))
      (node (ref "U6") (pin "2") (pinfunction "K_2") (pintype "passive"))
    )
    (net (code "77") (name "Net-(U8-PB6_(XTAL1{slash}TOSC1))") (class "Default")
      (node (ref "C3") (pin "1") (pinfunction "1_1") (pintype "passive"))
      (node (ref "U8") (pin "7") (pinfunction "PB6_(XTAL1/TOSC1)_7") (pintype "passive"))
      (node (ref "Y3") (pin "1") (pinfunction "1_1") (pintype "passive"))
    )
    (net (code "78") (name "Net-(U8-PB7_(XTAL2{slash}TOSC2))") (class "Default")
      (node (ref "C4") (pin "1") (pinfunction "1_1") (pintype "passive"))
      (node (ref "U8") (pin "8") (pinfunction "PB7_(XTAL2/TOSC2)_8") (pintype "passive"))
      (node (ref "Y3") (pin "2") (pinfunction "2_2") (pintype "passive"))
    )
    (net (code "79") (name "Net-(U9-CLK_IN)") (class "Default")
      (node (ref "C32") (pin "1") (pinfunction "1_1") (pintype "passive"))
      (node (ref "U9") (pin "15") (pinfunction "CLK_IN_15") (pintype "passive"))
      (node (ref "Y1") (pin "1") (pinfunction "1_1") (pintype "passive"))
    )
    (net (code "80") (name "Net-(U9-CLK_OUT)") (class "Default")
      (node (ref "C33") (pin "1") (pinfunction "1_1") (pintype "passive"))
      (node (ref "U9") (pin "16") (pinfunction "CLK_OUT_16") (pintype "passive"))
      (node (ref "Y1") (pin "2") (pinfunction "2_2") (pintype "passive"))
    )
    (net (code "81") (name "Net-(U9-DIN)") (class "Default")
      (node (ref "R42") (pin "2") (pinfunction "2_2") (pintype "passive"))
      (node (ref "R50") (pin "1") (pinfunction "1_1") (pintype "passive"))
      (node (ref "U9") (pin "20") (pinfunction "DIN_20") (pintype "passive"))
    )
    (net (code "82") (name "Net-(U9-DOUT)") (class "Default")
      (node (ref "R43") (pin "2") (pinfunction "2_2") (pintype "passive"))
      (node (ref "R51") (pin "1") (pinfunction "1_1") (pintype "passive"))
      (node (ref "U9") (pin "19") (pinfunction "DOUT_19") (pintype "passive"))
    )
    (net (code "83") (name "Net-(U9-REF_IN{slash}OUT)") (class "Default")
      (node (ref "C26") (pin "1") (pinfunction "1_1") (pintype "passive"))
      (node (ref "U9") (pin "9") (pinfunction "REF_IN/OUT_9") (pintype "passive"))
    )
    (net (code "84") (name "Net-(U9-SCLK)") (class "Default")
      (node (ref "R44") (pin "2") (pinfunction "2_2") (pintype "passive"))
      (node (ref "R52") (pin "1") (pinfunction "1_1") (pintype "passive"))
      (node (ref "U9") (pin "18") (pinfunction "SCLK_18") (pintype "passive"))
    )
    (net (code "85") (name "Net-(U9-V1N)") (class "Default")
      (node (ref "C28") (pin "1") (pinfunction "1_1") (pintype "passive"))
      (node (ref "R38") (pin "1") (pinfunction "1_1") (pintype "passive"))
      (node (ref "U9") (pin "5") (pinfunction "V1N_5") (pintype "passive"))
    )
    (net (code "86") (name "Net-(U9-V1P)") (class "Default")
      (node (ref "C27") (pin "1") (pinfunction "1_1") (pintype "passive"))
      (node (ref "R37") (pin "1") (pinfunction "1_1") (pintype "passive"))
      (node (ref "U9") (pin "4") (pinfunction "V1P_4") (pintype "passive"))
    )
    (net (code "87") (name "Net-(U9-V2N)") (class "Default")
      (node (ref "C29") (pin "1") (pinfunction "1_1") (pintype "passive"))
      (node (ref "R39") (pin "1") (pinfunction "1_1") (pintype "passive"))
      (node (ref "U9") (pin "6") (pinfunction "V2N_6") (pintype "passive"))
    )
    (net (code "88") (name "Net-(U9-V2P)") (class "Default")
      (node (ref "C30") (pin "1") (pinfunction "1_1") (pintype "passive"))
      (node (ref "R40") (pin "2") (pinfunction "2_2") (pintype "passive"))
      (node (ref "U9") (pin "7") (pinfunction "V2P_7") (pintype "passive"))
      (node (ref "VR2") (pin "2") (pinfunction "TAP_2") (pintype "passive"))
      (node (ref "VR2") (pin "3") (pinfunction "BOT_3") (pintype "passive"))
    )
    (net (code "89") (name "Net-(U9-~{CS})") (class "Default")
      (node (ref "R45") (pin "2") (pinfunction "2_2") (pintype "passive"))
      (node (ref "U9") (pin "17") (pinfunction "~{CS}_17") (pintype "passive"))
    )
    (net (code "90") (name "Net-(U9-~{RESET})") (class "Default")
      (node (ref "R1") (pin "1") (pinfunction "1_1") (pintype "passive"))
      (node (ref "U9") (pin "1") (pinfunction "~{RESET}_1") (pintype "passive"))
    )
    (net (code "91") (name "Net-(U10-X1)") (class "Default")
      (node (ref "U10") (pin "1") (pinfunction "X1_1") (pintype "input"))
      (node (ref "Y2") (pin "1") (pinfunction "OSC1_1") (pintype "passive"))
    )
    (net (code "92") (name "Net-(U10-X2)") (class "Default")
      (node (ref "U10") (pin "2") (pinfunction "X2_2") (pintype "output"))
      (node (ref "Y2") (pin "2") (pinfunction "OSC2_2") (pintype "passive"))
    )
    (net (code "93") (name "Net-(VR1-TAP)") (class "Default")
      (node (ref "R37") (pin "2") (pinfunction "2_2") (pintype "passive"))
      (node (ref "VR1") (pin "2") (pinfunction "TAP_2") (pintype "passive"))
    )
    (net (code "94") (name "Net-(VR2-TOP)") (class "Default")
      (node (ref "R36") (pin "1") (pinfunction "1_1") (pintype "passive"))
      (node (ref "VR2") (pin "1") (pinfunction "TOP_1") (pintype "passive"))
    )
    (net (code "95") (name "PHASE") (class "Default")
      (node (ref "C2") (pin "1") (pinfunction "1_1") (pintype "passive"))
      (node (ref "C9") (pin "1") (pinfunction "1_1") (pintype "passive"))
      (node (ref "F1") (pin "2") (pinfunction "2_2") (pintype "passive"))
      (node (ref "L4") (pin "1") (pinfunction "1_1") (pintype "passive"))
      (node (ref "R2") (pin "2") (pinfunction "2_2") (pintype "passive"))
      (node (ref "R32") (pin "1") (pinfunction "1_1") (pintype "passive"))
    )
    (net (code "96") (name "PHASEIN") (class "Default")
      (node (ref "F1") (pin "1") (pinfunction "1_1") (pintype "passive"))
    )
    (net (code "97") (name "PHASE_FIR") (class "Default")
      (node (ref "C20") (pin "1") (pinfunction "1_1") (pintype "passive"))
      (node (ref "C22") (pin "2") (pinfunction "2_2") (pintype "passive"))
      (node (ref "JP2000") (pin "2") (pinfunction "2_2") (pintype "passive"))
      (node (ref "K1") (pin "1") (pinfunction "COM_1") (pintype "passive"))
      (node (ref "Q2") (pin "1") (pinfunction "T_1") (pintype "passive"))
      (node (ref "Q3") (pin "1") (pinfunction "T_1") (pintype "passive"))
      (node (ref "R18") (pin "1") (pinfunction "1_1") (pintype "passive"))
      (node (ref "R36") (pin "2") (pinfunction "2_2") (pintype "passive"))
      (node (ref "R8") (pin "2") (pinfunction "2_2") (pintype "passive"))
    )
    (net (code "98") (name "POWERIN") (class "Default")
      (node (ref "D5") (pin "2") (pinfunction "2_2") (pintype "passive"))
      (node (ref "J1") (pin "1") (pinfunction "1_1") (pintype "passive"))
      (node (ref "Q4") (pin "2") (pinfunction "E_2") (pintype "passive"))
      (node (ref "R16") (pin "1") (pinfunction "1_1") (pintype "passive"))
      (node (ref "R7") (pin "2") (pinfunction "2_2") (pintype "passive"))
      (node (ref "U1") (pin "6") (pinfunction "+DC_OUT_6") (pintype "passive"))
      (node (ref "U3") (pin "1") (pinfunction "Vin_1") (pintype "passive"))
    )
    (net (code "99") (name "VDD5") (class "Default")
      (node (ref "C21") (pin "1") (pinfunction "1_1") (pintype "passive"))
      (node (ref "C23") (pin "2") (pinfunction "2_2") (pintype "passive"))
      (node (ref "C6") (pin "1") (pinfunction "1_1") (pintype "passive"))
      (node (ref "J1") (pin "29") (pinfunction "29_29") (pintype "passive"))
      (node (ref "L1") (pin "1") (pinfunction "1_1") (pintype "passive"))
      (node (ref "R26") (pin "1") (pinfunction "1_1") (pintype "passive"))
      (node (ref "R27") (pin "1") (pinfunction "1_1") (pintype "passive"))
      (node (ref "U3") (pin "3") (pinfunction "+5V_3") (pintype "passive"))
      (node (ref "U9") (pin "3") (pinfunction "AVDD_3") (pintype "passive"))
    )
    (net (code "100") (name "VDD5D") (class "Default")
      (node (ref "C11") (pin "1") (pinfunction "1_1") (pintype "passive"))
      (node (ref "C8") (pin "2") (pinfunction "2_2") (pintype "passive"))
      (node (ref "JP2") (pin "2") (pinfunction "2_2") (pintype "passive"))
      (node (ref "L1") (pin "2") (pinfunction "2_2") (pintype "passive"))
      (node (ref "R13") (pin "2") (pinfunction "2_2") (pintype "passive"))
      (node (ref "R21") (pin "2") (pinfunction "2_2") (pintype "passive"))
      (node (ref "R30") (pin "2") (pinfunction "2_2") (pintype "passive"))
      (node (ref "R46") (pin "2") (pinfunction "2_2") (pintype "passive"))
      (node (ref "R47") (pin "2") (pinfunction "2_2") (pintype "passive"))
      (node (ref "R48") (pin "2") (pinfunction "2_2") (pintype "passive"))
      (node (ref "U10") (pin "8") (pinfunction "VCC_8") (pintype "power_in"))
      (node (ref "U8") (pin "18") (pinfunction "AVCC_18") (pintype "passive"))
      (node (ref "U8") (pin "20") (pinfunction "AREF_20") (pintype "passive"))
      (node (ref "U8") (pin "4") (pinfunction "VCC_4") (pintype "passive"))
      (node (ref "U8") (pin "6") (pinfunction "VCC_6") (pintype "input"))
      (node (ref "U9") (pin "2") (pinfunction "DVDD_2") (pintype "passive"))
    )
    (net (code "101") (name "unconnected-(H1-Pad5)") (class "Default")
      (node (ref "H1") (pin "5") (pinfunction "5_5") (pintype "passive"))
    )
    (net (code "102") (name "unconnected-(H1-Pad6)") (class "Default")
      (node (ref "H1") (pin "6") (pinfunction "6_6") (pintype "passive"))
    )
    (net (code "103") (name "unconnected-(H1-VCC-Pad1)") (class "Default")
      (node (ref "H1") (pin "1") (pinfunction "VCC_1") (pintype "passive"))
    )
    (net (code "104") (name "unconnected-(J3-VCC-Pad1)") (class "Default")
      (node (ref "J3") (pin "1") (pinfunction "VCC_1") (pintype "input"))
    )
    (net (code "105") (name "unconnected-(K1-NO-Pad3)") (class "Default")
      (node (ref "K1") (pin "3") (pinfunction "NO_3") (pintype "passive"))
    )
    (net (code "106") (name "unconnected-(U8-ADC6-Pad19)") (class "Default")
      (node (ref "U8") (pin "19") (pinfunction "ADC6_19") (pintype "input"))
    )
    (net (code "107") (name "unconnected-(U8-ADC7-Pad22)") (class "Default")
      (node (ref "U8") (pin "22") (pinfunction "ADC7_22") (pintype "input"))
    )
    (net (code "108") (name "unconnected-(U8-PC0_(ADC0)-Pad23)") (class "Default")
      (node (ref "U8") (pin "23") (pinfunction "PC0_(ADC0)_23") (pintype "passive"))
    )
    (net (code "109") (name "unconnected-(U8-PC3_(ADC3)-Pad26)") (class "Default")
      (node (ref "U8") (pin "26") (pinfunction "PC3_(ADC3)_26") (pintype "passive"))
    )
    (net (code "110") (name "unconnected-(U8-PC4_(ADC4{slash}SDA)-Pad27)") (class "Default")
      (node (ref "U8") (pin "27") (pinfunction "PC4_(ADC4/SDA)_27") (pintype "passive"))
    )
    (net (code "111") (name "unconnected-(U8-PC5_(ADC5{slash}SCL)-Pad28)") (class "Default")
      (node (ref "U8") (pin "28") (pinfunction "PC5_(ADC5/SCL)_28") (pintype "passive"))
    )
    (net (code "112") (name "unconnected-(U8-PD4_(XCK{slash}T0)-Pad2)") (class "Default")
      (node (ref "U8") (pin "2") (pinfunction "PD4_(XCK/T0)_2") (pintype "passive"))
    )
    (net (code "113") (name "unconnected-(U8-PD7_(AIN1)-Pad11)") (class "Default")
      (node (ref "U8") (pin "11") (pinfunction "PD7_(AIN1)_11") (pintype "passive"))
    )
    (net (code "114") (name "unconnected-(U9-~{SAG}-Pad13)") (class "Default")
      (node (ref "U9") (pin "13") (pinfunction "~{SAG}_13") (pintype "passive"))
    )
  )
)
